# Power.net
KiCad netlist of a schematic drawn in Altium Designer
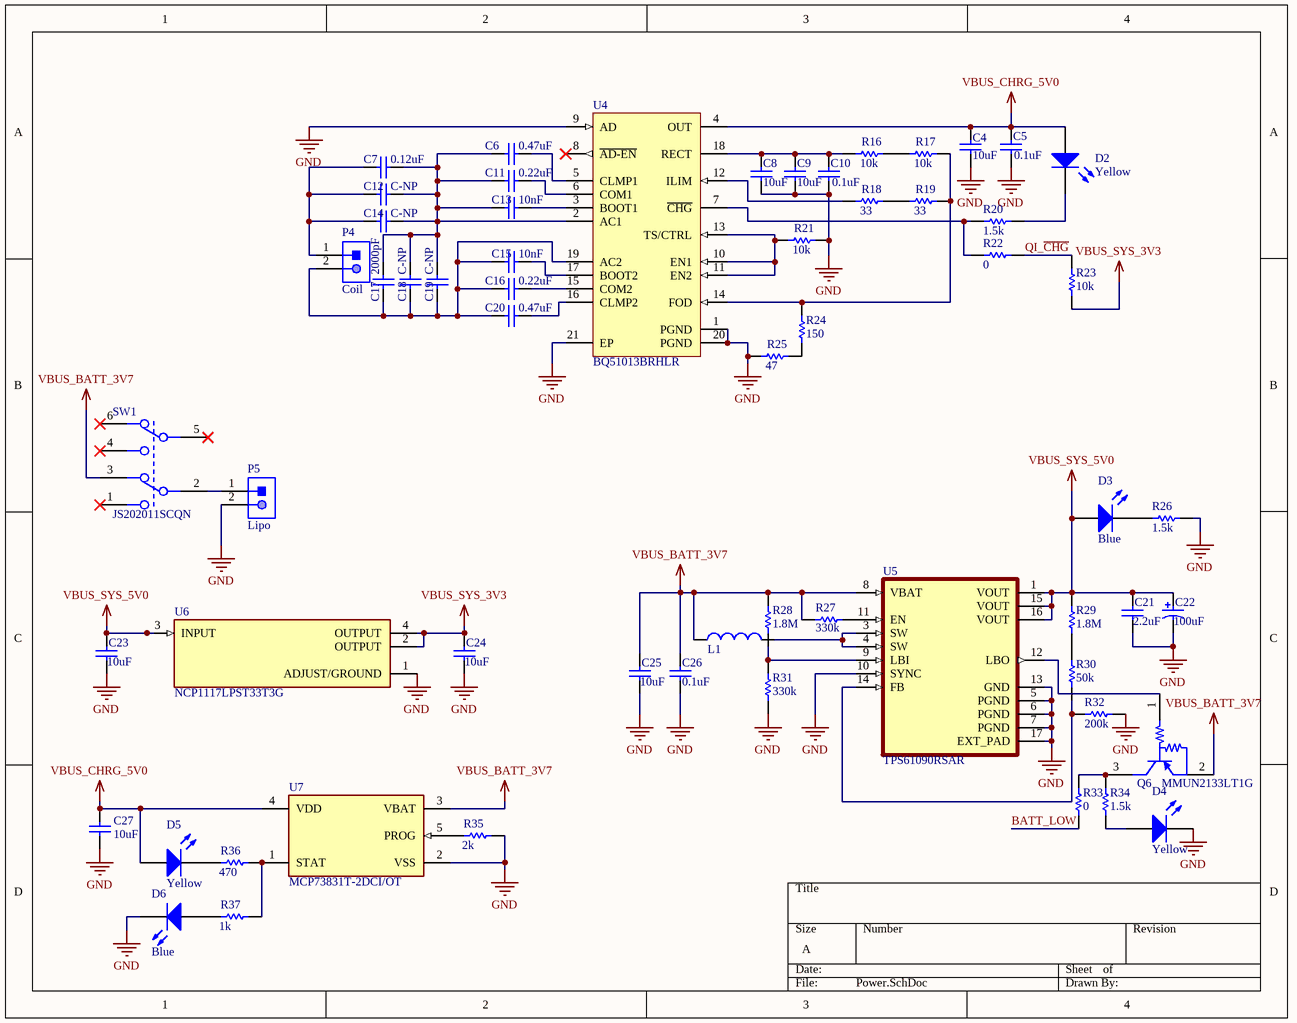
[diagram p0: Power.SchDoc]

(export (version "E")
  (design (tool "Eeschema 10.0.6"))
  (components
    (comp (ref "C4")
      (value "10uF")
      (footprint "0603")
      (description "10uF, 10%, 25V")
      (fields (field (name "GFUPARTNO") "C1608C0G1H361J"))
      (libsource (lib "AltiumGFU") (part "Cap"))
    )
    (comp (ref "C5")
      (value "0.1uF")
      (footprint "0603")
      (description "0.1uF, 10%, 50V")
      (fields (field (name "GFUPARTNO") "C1608C0G1H361J"))
      (libsource (lib "AltiumGFU") (part "Cap"))
    )
    (comp (ref "C6")
      (value "0.47uF")
      (footprint "0603")
      (description "0.47uF, 10%, 25V")
      (fields (field (name "GFUPARTNO") "C1608C0G1H361J"))
      (libsource (lib "AltiumGFU") (part "Cap"))
    )
    (comp (ref "C7")
      (value "0.12uF")
      (footprint "0603")
      (description "0.12 uF, 10%, 25V")
      (fields (field (name "GFUPARTNO") "C1608C0G1H361J"))
      (libsource (lib "AltiumGFU") (part "Cap"))
    )
    (comp (ref "C8")
      (value "10uF")
      (footprint "0603")
      (description "10uF, 10%, 25V")
      (fields (field (name "GFUPARTNO") "C1608C0G1H361J"))
      (libsource (lib "AltiumGFU") (part "Cap"))
    )
    (comp (ref "C9")
      (value "10uF")
      (footprint "0603")
      (description "10uF, 10%, 25V")
      (fields (field (name "GFUPARTNO") "C1608C0G1H361J"))
      (libsource (lib "AltiumGFU") (part "Cap"))
    )
    (comp (ref "C10")
      (value "0.1uF")
      (footprint "0603")
      (description "0.1uF, 10%, 50V")
      (fields (field (name "GFUPARTNO") "C1608C0G1H361J"))
      (libsource (lib "AltiumGFU") (part "Cap"))
    )
    (comp (ref "C11")
      (value "0.22uF")
      (footprint "0603")
      (description "0.22uF, 10%, 25V")
      (fields (field (name "GFUPARTNO") "C1608C0G1H361J"))
      (libsource (lib "AltiumGFU") (part "Cap"))
    )
    (comp (ref "C12")
      (value "C-NP")
      (footprint "0603")
      (description "0.12 uF, 10%, 25V")
      (fields (field (name "GFUPARTNO") "C1608C0G1H361J"))
      (libsource (lib "AltiumGFU") (part "Cap"))
    )
    (comp (ref "C13")
      (value "10nF")
      (footprint "0603")
      (description "10nF, 10%, 25V")
      (fields (field (name "GFUPARTNO") "C1608C0G1H361J"))
      (libsource (lib "AltiumGFU") (part "Cap"))
    )
    (comp (ref "C14")
      (value "C-NP")
      (footprint "0603")
      (description "0.12 uF, 10%, 25V")
      (fields (field (name "GFUPARTNO") "C1608C0G1H361J"))
      (libsource (lib "AltiumGFU") (part "Cap"))
    )
    (comp (ref "C15")
      (value "10nF")
      (footprint "0603")
      (description "10nF, 10%, 25V")
      (fields (field (name "GFUPARTNO") "C1608C0G1H361J"))
      (libsource (lib "AltiumGFU") (part "Cap"))
    )
    (comp (ref "C16")
      (value "0.22uF")
      (footprint "0603")
      (description "0.22uF, 10%, 25V")
      (fields (field (name "GFUPARTNO") "C1608C0G1H361J"))
      (libsource (lib "AltiumGFU") (part "Cap"))
    )
    (comp (ref "C17")
      (value "2000pF")
      (footprint "0603")
      (description "2000 pF, 10%, 50V")
      (fields (field (name "GFUPARTNO") "C1608C0G1H361J"))
      (libsource (lib "AltiumGFU") (part "Cap"))
    )
    (comp (ref "C18")
      (value "C-NP")
      (footprint "0603")
      (description "2000 pF, 10%, 50V")
      (fields (field (name "GFUPARTNO") "C1608C0G1H361J"))
      (libsource (lib "AltiumGFU") (part "Cap"))
    )
    (comp (ref "C19")
      (value "C-NP")
      (footprint "0603")
      (description "2000 pF, 10%, 50V")
      (fields (field (name "GFUPARTNO") "C1608C0G1H361J"))
      (libsource (lib "AltiumGFU") (part "Cap"))
    )
    (comp (ref "C20")
      (value "0.47uF")
      (footprint "0603")
      (description "0.47uF, 10%, 25V")
      (fields (field (name "GFUPARTNO") "C1608C0G1H361J"))
      (libsource (lib "AltiumGFU") (part "Cap"))
    )
    (comp (ref "C21")
      (value "2.2uF")
      (footprint "0805")
      (description "1.5nF, 10%, 50V")
      (fields (field (name "GFUPARTNO") "CC0805KRX7R9BB152"))
      (libsource (lib "AltiumGFU") (part "Cap"))
    )
    (comp (ref "C22")
      (value "100uF")
      (footprint "PNSC-FP-V-C_V")
      (description "EEE-HA Series 6.3 V 100 uF Ø 5 x 5.4 mm 105 °C SMT V-Chip Aluminum Electrolytic. EEE-HA0J101WR")
      (fields (field (name "MANUFACTURER") "Panasonic"))
      (libsource (lib "Altium Content Vault") (part "CAP-P-2"))
    )
    (comp (ref "C23")
      (value "10uF")
      (footprint "0805")
      (description "1.5nF, 10%, 50V")
      (fields (field (name "GFUPARTNO") "CC0805KRX7R9BB152"))
      (libsource (lib "AltiumGFU") (part "Cap"))
    )
    (comp (ref "C24")
      (value "10uF")
      (footprint "0805")
      (description "1.5nF, 10%, 50V")
      (fields (field (name "GFUPARTNO") "CC0805KRX7R9BB152"))
      (libsource (lib "AltiumGFU") (part "Cap"))
    )
    (comp (ref "C25")
      (value "10uF")
      (footprint "0805")
      (description "1.5nF, 10%, 50V")
      (fields (field (name "GFUPARTNO") "CC0805KRX7R9BB152"))
      (libsource (lib "AltiumGFU") (part "Cap"))
    )
    (comp (ref "C26")
      (value "0.1uF")
      (footprint "0805")
      (description "1.5nF, 10%, 50V")
      (fields (field (name "GFUPARTNO") "CC0805KRX7R9BB152"))
      (libsource (lib "AltiumGFU") (part "Cap"))
    )
    (comp (ref "C27")
      (value "10uF")
      (footprint "0805")
      (description "1.5nF, 10%, 50V")
      (fields (field (name "GFUPARTNO") "CC0805KRX7R9BB152"))
      (libsource (lib "AltiumGFU") (part "Cap"))
    )
    (comp (ref "D2")
      (value "Yellow")
      (footprint "1206_A_LED")
      (libsource (lib "WE-LED_K1A2-2") (part "WE-LED_K1A2-2_Local"))
    )
    (comp (ref "D3")
      (value "Blue")
      (footprint "1206_A_LED")
      (libsource (lib "WE-LED_K1A2-2") (part "WE-LED_K1A2-2_Local"))
    )
    (comp (ref "D4")
      (value "Yellow")
      (footprint "1206_A_LED")
      (libsource (lib "WE-LED_K1A2-2") (part "WE-LED_K1A2-2_Local"))
    )
    (comp (ref "D5")
      (value "Yellow")
      (footprint "1206_A_LED")
      (libsource (lib "WE-LED_K1A2-2") (part "WE-LED_K1A2-2_Local"))
    )
    (comp (ref "D6")
      (value "Blue")
      (footprint "1206_A_LED")
      (libsource (lib "WE-LED_K1A2-2") (part "WE-LED_K1A2-2_Local"))
    )
    (comp (ref "L1")
      (value "MSS6132-472MLB")
      (footprint "COILCRAFT MSS6132 SERIES")
      (description "INDUCTOR POWER 4.7UH SHIELDED SMD")
      (fields (field (name "TOLERANCE") "20%"))
      (libsource (lib "AltiumGFU") (part "Inductor"))
    )
    (comp (ref "P4")
      (value "Coil")
      (footprint "JST-S2B-PH-K-S_V")
      (fields (field (name "TOLERANCE") "20%"))
      (libsource (lib "Altium Content Vault") (part "CN-1P-M-R2"))
    )
    (comp (ref "P5")
      (value "Lipo")
      (footprint "JST-S2B-PH-K-S_V")
      (fields (field (name "TOLERANCE") "20%"))
      (libsource (lib "Altium Content Vault") (part "CN-1P-M-R2"))
    )
    (comp (ref "Q6")
      (value "MMUN2133LT1G")
      (footprint "ONSC-SOT-23-3-318-08_V")
      (fields (field (name "MANUFACTURER") "On Semiconductor"))
      (libsource (lib "Altium Content Vault") (part "ONSC-BRT-PNP-B1E2C3-3_A"))
    )
    (comp (ref "R16")
      (value "10k")
      (footprint "0603_RES_HD")
      (description "RES 10k OHM 1/10W 5% 0603 SMD")
      (fields (field (name "GFUPARTNO") "RC0603JR-0718RL"))
      (libsource (lib "AltiumGFU") (part "ResBasic"))
    )
    (comp (ref "R17")
      (value "10k")
      (footprint "0603_RES_HD")
      (description "RES 10k OHM 1/10W 5% 0603 SMD")
      (fields (field (name "GFUPARTNO") "RC0603JR-0718RL"))
      (libsource (lib "AltiumGFU") (part "ResBasic"))
    )
    (comp (ref "R18")
      (value "33")
      (footprint "0603_RES_HD")
      (description "RES 33 OHM 1/10W 5% 0603 SMD")
      (fields (field (name "GFUPARTNO") "RC0603JR-0718RL"))
      (libsource (lib "AltiumGFU") (part "ResBasic"))
    )
    (comp (ref "R19")
      (value "33")
      (footprint "0603_RES_HD")
      (description "RES 33 OHM 1/10W 5% 0603 SMD")
      (fields (field (name "GFUPARTNO") "RC0603JR-0718RL"))
      (libsource (lib "AltiumGFU") (part "ResBasic"))
    )
    (comp (ref "R20")
      (value "1.5k")
      (footprint "0603_RES_HD")
      (description "RES 1.5k OHM 1/10W 5% 0603 SMD")
      (fields (field (name "GFUPARTNO") "RC0603JR-0718RL"))
      (libsource (lib "AltiumGFU") (part "ResBasic"))
    )
    (comp (ref "R21")
      (value "10k")
      (footprint "0603_RES_HD")
      (description "RES 10k OHM 1/10W 5% 0603 SMD")
      (fields (field (name "GFUPARTNO") "RC0603JR-0718RL"))
      (libsource (lib "AltiumGFU") (part "ResBasic"))
    )
    (comp (ref "R22")
      (value "0")
      (footprint "0603_RES_HD")
      (description "RES 1.5k OHM 1/10W 5% 0603 SMD")
      (fields (field (name "GFUPARTNO") "RC0603JR-0718RL"))
      (libsource (lib "AltiumGFU") (part "ResBasic"))
    )
    (comp (ref "R23")
      (value "10k")
      (footprint "0603_RES_HD")
      (description "RES 1.5k OHM 1/10W 5% 0603 SMD")
      (fields (field (name "GFUPARTNO") "RC0603JR-0718RL"))
      (libsource (lib "AltiumGFU") (part "ResBasic"))
    )
    (comp (ref "R24")
      (value "150")
      (footprint "0603_RES_HD")
      (description "RES 150 OHM 1/10W 5% 0603 SMD")
      (fields (field (name "GFUPARTNO") "RC0603JR-0718RL"))
      (libsource (lib "AltiumGFU") (part "ResBasic"))
    )
    (comp (ref "R25")
      (value "47")
      (footprint "0603_RES_HD")
      (description "RES 47 OHM 1/10W 5% 0603 SMD")
      (fields (field (name "GFUPARTNO") "RC0603JR-0718RL"))
      (libsource (lib "AltiumGFU") (part "ResBasic"))
    )
    (comp (ref "R26")
      (value "1.5k")
      (footprint "0805_RES_HD")
      (description "1.5kOhm ±1% 0.125W, 1/8W Surface Mount Resistor Thick Film ±100ppm/°C 0805")
      (fields (field (name "GFUPARTNO") "RC0805FR-07100RL"))
      (libsource (lib "AltiumGFU") (part "ResBasic"))
    )
    (comp (ref "R27")
      (value "330k")
      (footprint "0805_RES_HD")
      (description "330kOhm ±1% 0.125W, 1/8W Surface Mount Resistor Thick Film ±100ppm/°C 0805")
      (fields (field (name "GFUPARTNO") "RC0805FR-07100RL"))
      (libsource (lib "AltiumGFU") (part "ResBasic"))
    )
    (comp (ref "R28")
      (value "1.8M")
      (footprint "0805_RES_HD")
      (description "1.8MOhm ±1% 0.125W, 1/8W Surface Mount Resistor Thick Film ±100ppm/°C 0805")
      (fields (field (name "GFUPARTNO") "RC0805FR-07100RL"))
      (libsource (lib "AltiumGFU") (part "ResBasic"))
    )
    (comp (ref "R29")
      (value "1.8M")
      (footprint "0805_RES_HD")
      (description "100 Ohm ±1% 0.125W, 1/8W Surface Mount Resistor Thick Film ±100ppm/°C 0805")
      (fields (field (name "GFUPARTNO") "RC0805FR-07100RL"))
      (libsource (lib "AltiumGFU") (part "ResBasic"))
    )
    (comp (ref "R30")
      (value "50k")
      (footprint "0805_RES_HD")
      (description "50k Ohm ±1% 0.125W, 1/8W Surface Mount Resistor Thick Film ±100ppm/°C 0805")
      (fields (field (name "GFUPARTNO") "RC0805FR-07100RL"))
      (libsource (lib "AltiumGFU") (part "ResBasic"))
    )
    (comp (ref "R31")
      (value "330k")
      (footprint "0805_RES_HD")
      (description "330kOhm ±1% 0.125W, 1/8W Surface Mount Resistor Thick Film ±100ppm/°C 0805")
      (fields (field (name "GFUPARTNO") "RC0805FR-07100RL"))
      (libsource (lib "AltiumGFU") (part "ResBasic"))
    )
    (comp (ref "R32")
      (value "200k")
      (footprint "0805_RES_HD")
      (description "50k Ohm ±1% 0.125W, 1/8W Surface Mount Resistor Thick Film ±100ppm/°C 0805")
      (fields (field (name "GFUPARTNO") "RC0805FR-07100RL"))
      (libsource (lib "AltiumGFU") (part "ResBasic"))
    )
    (comp (ref "R33")
      (value "0")
      (footprint "0805_RES_HD")
      (description "1.5kOhm ±1% 0.125W, 1/8W Surface Mount Resistor Thick Film ±100ppm/°C 0805")
      (fields (field (name "GFUPARTNO") "RC0805FR-07100RL"))
      (libsource (lib "AltiumGFU") (part "ResBasic"))
    )
    (comp (ref "R34")
      (value "1.5k")
      (footprint "0805_RES_HD")
      (description "1.5kOhm ±1% 0.125W, 1/8W Surface Mount Resistor Thick Film ±100ppm/°C 0805")
      (fields (field (name "GFUPARTNO") "RC0805FR-07100RL"))
      (libsource (lib "AltiumGFU") (part "ResBasic"))
    )
    (comp (ref "R35")
      (value "2k")
      (footprint "0805_RES_HD")
      (description "20kOhm ±1% 0.125W, 1/8W Surface Mount Resistor Thick Film ±100ppm/°C 0805")
      (fields (field (name "GFUPARTNO") "RC0805FR-07100RL"))
      (libsource (lib "AltiumGFU") (part "ResBasic"))
    )
    (comp (ref "R36")
      (value "470")
      (footprint "0805_RES_HD")
      (description "470Ohm ±1% 0.125W, 1/8W Surface Mount Resistor Thick Film ±100ppm/°C 0805")
      (fields (field (name "GFUPARTNO") "RC0805FR-07100RL"))
      (libsource (lib "AltiumGFU") (part "ResBasic"))
    )
    (comp (ref "R37")
      (value "1k")
      (footprint "0805_RES_HD")
      (description "470Ohm ±1% 0.125W, 1/8W Surface Mount Resistor Thick Film ±100ppm/°C 0805")
      (fields (field (name "GFUPARTNO") "RC0805FR-07100RL"))
      (libsource (lib "AltiumGFU") (part "ResBasic"))
    )
    (comp (ref "SW1")
      (value "JS202011SCQN")
      (footprint "FP-JS202011SCQN-MFG")
      (description "SWITCH SLIDE DPDT 300MA 6V")
      (libsource (lib "Altium Content Vault") (part "ac99ea1af431c19115f5225061c5c88"))
    )
    (comp (ref "U4")
      (value "BQ51013BRHLR")
      (footprint "RHL0020A_V")
      (fields (field (name "PARTNUMBER") "BQ51013B"))
      (libsource (lib "Altium Content Vault") (part "TI-BQ51013B-RHL20"))
    )
    (comp (ref "U5")
      (value "TPS61090RSAR")
      (footprint "QFN65P400X400X100-17N")
      (description "1.8Vin, 2A Switch, 96% Efficient Boost Converter 16-QFN -40 to 85")
      (fields (field (name "MF") "Texas Instruments"))
      (libsource (lib "TPS61090RSAR") (part "TPS61090RSAR"))
    )
    (comp (ref "U6")
      (value "NCP1117LPST33T3G")
      (footprint "FP-318H-MFG")
      (description "IC REG LINEAR 3.3V 1A SOT223")
      (libsource (lib "Altium Content Vault") (part "ba9dfc6f1948e29eb9591bef83395b3"))
    )
    (comp (ref "U7")
      (value "MCP73831T-2DCI/OT")
      (footprint "FP-C04-091-OT-IPC_B")
      (description "IC CONTROLLR LI-ION 4.2V SOT23-5")
      (libsource (lib "Altium Content Vault") (part "61f5a3bb3429d9e0caadea342aa3b19"))
    )
  )
  (nets
    (net (code "1") (name "/BATT_LOW") (class "Default")
      (node (ref "R33") (pin "1") (pinfunction "1_1") (pintype "passive"))
    )
    (net (code "2") (name "/QI_~{CHG}") (class "Default")
      (node (ref "R22") (pin "1") (pinfunction "1_1") (pintype "passive"))
      (node (ref "R23") (pin "2") (pinfunction "2_2") (pintype "passive"))
    )
    (net (code "3") (name "GND") (class "Default")
      (node (ref "C10") (pin "1") (pinfunction "1_1") (pintype "passive"))
      (node (ref "C21") (pin "2") (pinfunction "2_2") (pintype "passive"))
      (node (ref "C22") (pin "2") (pinfunction "2_2") (pintype "passive"))
      (node (ref "C23") (pin "2") (pinfunction "2_2") (pintype "passive"))
      (node (ref "C24") (pin "2") (pinfunction "2_2") (pintype "passive"))
      (node (ref "C25") (pin "2") (pinfunction "2_2") (pintype "passive"))
      (node (ref "C26") (pin "2") (pinfunction "2_2") (pintype "passive"))
      (node (ref "C27") (pin "2") (pinfunction "2_2") (pintype "passive"))
      (node (ref "C4") (pin "1") (pinfunction "1_1") (pintype "passive"))
      (node (ref "C5") (pin "1") (pinfunction "1_1") (pintype "passive"))
      (node (ref "C8") (pin "1") (pinfunction "1_1") (pintype "passive"))
      (node (ref "C9") (pin "1") (pinfunction "1_1") (pintype "passive"))
      (node (ref "D4") (pin "1") (pinfunction "K_1") (pintype "passive"))
      (node (ref "D6") (pin "1") (pinfunction "K_1") (pintype "passive"))
      (node (ref "P5") (pin "2") (pinfunction "2_2") (pintype "passive"))
      (node (ref "R21") (pin "2") (pinfunction "2_2") (pintype "passive"))
      (node (ref "R25") (pin "1") (pinfunction "1_1") (pintype "passive"))
      (node (ref "R26") (pin "1") (pinfunction "1_1") (pintype "passive"))
      (node (ref "R31") (pin "1") (pinfunction "1_1") (pintype "passive"))
      (node (ref "R32") (pin "2") (pinfunction "2_2") (pintype "passive"))
      (node (ref "R35") (pin "2") (pinfunction "2_2") (pintype "passive"))
      (node (ref "U4") (pin "1") (pinfunction "PGND_1") (pintype "power_in"))
      (node (ref "U4") (pin "20") (pinfunction "PGND_20") (pintype "power_in"))
      (node (ref "U4") (pin "21") (pinfunction "EP_21") (pintype "passive"))
      (node (ref "U4") (pin "9") (pinfunction "AD_9") (pintype "input"))
      (node (ref "U5") (pin "10") (pinfunction "SYNC_10") (pintype "input"))
      (node (ref "U5") (pin "13") (pinfunction "GND_13") (pintype "power_in"))
      (node (ref "U5") (pin "17") (pinfunction "EXT_PAD_17") (pintype "power_in"))
      (node (ref "U5") (pin "5") (pinfunction "PGND_5") (pintype "power_in"))
      (node (ref "U5") (pin "6") (pinfunction "PGND_6") (pintype "power_in"))
      (node (ref "U5") (pin "7") (pinfunction "PGND_7") (pintype "power_in"))
      (node (ref "U6") (pin "1") (pinfunction "ADJUST/GROUND_1") (pintype "power_in"))
      (node (ref "U7") (pin "2") (pinfunction "VSS_2") (pintype "power_in"))
    )
    (net (code "4") (name "Net-(C12-Pad2)") (class "Default")
      (node (ref "C12") (pin "2") (pinfunction "2_2") (pintype "passive"))
      (node (ref "C14") (pin "2") (pinfunction "2_2") (pintype "passive"))
      (node (ref "C7") (pin "2") (pinfunction "2_2") (pintype "passive"))
      (node (ref "P4") (pin "1") (pinfunction "1_1") (pintype "passive"))
    )
    (net (code "5") (name "Net-(D2-K)") (class "Default")
      (node (ref "D2") (pin "1") (pinfunction "K_1") (pintype "passive"))
      (node (ref "R20") (pin "1") (pinfunction "1_1") (pintype "passive"))
    )
    (net (code "6") (name "Net-(D3-K)") (class "Default")
      (node (ref "D3") (pin "1") (pinfunction "K_1") (pintype "passive"))
      (node (ref "R26") (pin "2") (pinfunction "2_2") (pintype "passive"))
    )
    (net (code "7") (name "Net-(D4-A)") (class "Default")
      (node (ref "D4") (pin "2") (pinfunction "A_2") (pintype "passive"))
      (node (ref "R34") (pin "1") (pinfunction "1_1") (pintype "passive"))
    )
    (net (code "8") (name "Net-(D5-K)") (class "Default")
      (node (ref "D5") (pin "1") (pinfunction "K_1") (pintype "passive"))
      (node (ref "R36") (pin "1") (pinfunction "1_1") (pintype "passive"))
    )
    (net (code "9") (name "Net-(D6-A)") (class "Default")
      (node (ref "D6") (pin "2") (pinfunction "A_2") (pintype "passive"))
      (node (ref "R37") (pin "1") (pinfunction "1_1") (pintype "passive"))
    )
    (net (code "10") (name "Net-(L1-Pad2)") (class "Default")
      (node (ref "L1") (pin "2") (pinfunction "2_2") (pintype "passive"))
      (node (ref "U5") (pin "3") (pinfunction "SW_3") (pintype "input"))
      (node (ref "U5") (pin "4") (pinfunction "SW_4") (pintype "input"))
    )
    (net (code "11") (name "Net-(P5-Pad1)") (class "Default")
      (node (ref "P5") (pin "1") (pinfunction "1_1") (pintype "passive"))
      (node (ref "SW1") (pin "2") (pinfunction "2_2") (pintype "passive"))
    )
    (net (code "12") (name "Net-(Q6-B)") (class "Default")
      (node (ref "Q6") (pin "1") (pinfunction "B_1") (pintype "passive"))
      (node (ref "U5") (pin "12") (pinfunction "LBO_12") (pintype "output"))
    )
    (net (code "13") (name "Net-(Q6-C)") (class "Default")
      (node (ref "Q6") (pin "3") (pinfunction "C_3") (pintype "passive"))
      (node (ref "R33") (pin "2") (pinfunction "2_2") (pintype "passive"))
      (node (ref "R34") (pin "2") (pinfunction "2_2") (pintype "passive"))
    )
    (net (code "14") (name "Net-(R16-Pad2)") (class "Default")
      (node (ref "R16") (pin "2") (pinfunction "2_2") (pintype "passive"))
      (node (ref "R17") (pin "1") (pinfunction "1_1") (pintype "passive"))
    )
    (net (code "15") (name "Net-(R18-Pad2)") (class "Default")
      (node (ref "R18") (pin "2") (pinfunction "2_2") (pintype "passive"))
      (node (ref "R19") (pin "1") (pinfunction "1_1") (pintype "passive"))
    )
    (net (code "16") (name "Net-(R24-Pad1)") (class "Default")
      (node (ref "R24") (pin "1") (pinfunction "1_1") (pintype "passive"))
      (node (ref "R25") (pin "2") (pinfunction "2_2") (pintype "passive"))
    )
    (net (code "17") (name "Net-(R29-Pad1)") (class "Default")
      (node (ref "R29") (pin "1") (pinfunction "1_1") (pintype "passive"))
      (node (ref "R30") (pin "1") (pinfunction "1_1") (pintype "passive"))
    )
    (net (code "18") (name "Net-(U4-AC1)") (class "Default")
      (node (ref "C11") (pin "2") (pinfunction "2_2") (pintype "passive"))
      (node (ref "C12") (pin "1") (pinfunction "1_1") (pintype "passive"))
      (node (ref "C13") (pin "2") (pinfunction "2_2") (pintype "passive"))
      (node (ref "C14") (pin "1") (pinfunction "1_1") (pintype "passive"))
      (node (ref "C17") (pin "1") (pinfunction "1_1") (pintype "passive"))
      (node (ref "C18") (pin "1") (pinfunction "1_1") (pintype "passive"))
      (node (ref "C19") (pin "1") (pinfunction "1_1") (pintype "passive"))
      (node (ref "C6") (pin "2") (pinfunction "2_2") (pintype "passive"))
      (node (ref "C7") (pin "1") (pinfunction "1_1") (pintype "passive"))
      (node (ref "U4") (pin "2") (pinfunction "AC1_2") (pintype "power_in"))
    )
    (net (code "19") (name "Net-(U4-AC2)") (class "Default")
      (node (ref "C15") (pin "2") (pinfunction "2_2") (pintype "passive"))
      (node (ref "C16") (pin "2") (pinfunction "2_2") (pintype "passive"))
      (node (ref "C17") (pin "2") (pinfunction "2_2") (pintype "passive"))
      (node (ref "C18") (pin "2") (pinfunction "2_2") (pintype "passive"))
      (node (ref "C19") (pin "2") (pinfunction "2_2") (pintype "passive"))
      (node (ref "C20") (pin "2") (pinfunction "2_2") (pintype "passive"))
      (node (ref "P4") (pin "2") (pinfunction "2_2") (pintype "passive"))
      (node (ref "U4") (pin "19") (pinfunction "AC2_19") (pintype "power_in"))
    )
    (net (code "20") (name "Net-(U4-BOOT1)") (class "Default")
      (node (ref "C13") (pin "1") (pinfunction "1_1") (pintype "passive"))
      (node (ref "U4") (pin "3") (pinfunction "BOOT1_3") (pintype "passive"))
    )
    (net (code "21") (name "Net-(U4-BOOT2)") (class "Default")
      (node (ref "C15") (pin "1") (pinfunction "1_1") (pintype "passive"))
      (node (ref "U4") (pin "17") (pinfunction "BOOT2_17") (pintype "passive"))
    )
    (net (code "22") (name "Net-(U4-CLMP1)") (class "Default")
      (node (ref "C6") (pin "1") (pinfunction "1_1") (pintype "passive"))
      (node (ref "U4") (pin "5") (pinfunction "CLMP1_5") (pintype "open_collector"))
    )
    (net (code "23") (name "Net-(U4-CLMP2)") (class "Default")
      (node (ref "C20") (pin "1") (pinfunction "1_1") (pintype "passive"))
      (node (ref "U4") (pin "16") (pinfunction "CLMP2_16") (pintype "open_collector"))
    )
    (net (code "24") (name "Net-(U4-COM1)") (class "Default")
      (node (ref "C11") (pin "1") (pinfunction "1_1") (pintype "passive"))
      (node (ref "U4") (pin "6") (pinfunction "COM1_6") (pintype "open_collector"))
    )
    (net (code "25") (name "Net-(U4-COM2)") (class "Default")
      (node (ref "C16") (pin "1") (pinfunction "1_1") (pintype "passive"))
      (node (ref "U4") (pin "15") (pinfunction "COM2_15") (pintype "open_collector"))
    )
    (net (code "26") (name "Net-(U4-EN1)") (class "Default")
      (node (ref "R21") (pin "1") (pinfunction "1_1") (pintype "passive"))
      (node (ref "U4") (pin "10") (pinfunction "EN1_10") (pintype "input"))
      (node (ref "U4") (pin "11") (pinfunction "EN2_11") (pintype "input"))
      (node (ref "U4") (pin "13") (pinfunction "TS/CTRL_13") (pintype "input"))
    )
    (net (code "27") (name "Net-(U4-FOD)") (class "Default")
      (node (ref "R17") (pin "2") (pinfunction "2_2") (pintype "passive"))
      (node (ref "R19") (pin "2") (pinfunction "2_2") (pintype "passive"))
      (node (ref "R24") (pin "2") (pinfunction "2_2") (pintype "passive"))
      (node (ref "U4") (pin "14") (pinfunction "FOD_14") (pintype "input"))
    )
    (net (code "28") (name "Net-(U4-ILIM)") (class "Default")
      (node (ref "R18") (pin "1") (pinfunction "1_1") (pintype "passive"))
      (node (ref "U4") (pin "12") (pinfunction "ILIM_12") (pintype "input"))
    )
    (net (code "29") (name "Net-(U4-RECT)") (class "Default")
      (node (ref "C10") (pin "2") (pinfunction "2_2") (pintype "passive"))
      (node (ref "C8") (pin "2") (pinfunction "2_2") (pintype "passive"))
      (node (ref "C9") (pin "2") (pinfunction "2_2") (pintype "passive"))
      (node (ref "R16") (pin "1") (pinfunction "1_1") (pintype "passive"))
      (node (ref "U4") (pin "18") (pinfunction "RECT_18") (pintype "passive"))
    )
    (net (code "30") (name "Net-(U4-~{CHG})") (class "Default")
      (node (ref "R20") (pin "2") (pinfunction "2_2") (pintype "passive"))
      (node (ref "R22") (pin "2") (pinfunction "2_2") (pintype "passive"))
      (node (ref "U4") (pin "7") (pinfunction "~{CHG}_7") (pintype "open_collector"))
    )
    (net (code "31") (name "Net-(U5-EN)") (class "Default")
      (node (ref "R27") (pin "2") (pinfunction "2_2") (pintype "passive"))
      (node (ref "U5") (pin "11") (pinfunction "EN_11") (pintype "input"))
    )
    (net (code "32") (name "Net-(U5-FB)") (class "Default")
      (node (ref "R30") (pin "2") (pinfunction "2_2") (pintype "passive"))
      (node (ref "R32") (pin "1") (pinfunction "1_1") (pintype "passive"))
      (node (ref "U5") (pin "14") (pinfunction "FB_14") (pintype "input"))
    )
    (net (code "33") (name "Net-(U5-LBI)") (class "Default")
      (node (ref "R28") (pin "1") (pinfunction "1_1") (pintype "passive"))
      (node (ref "R31") (pin "2") (pinfunction "2_2") (pintype "passive"))
      (node (ref "U5") (pin "9") (pinfunction "LBI_9") (pintype "input"))
    )
    (net (code "34") (name "Net-(U7-PROG)") (class "Default")
      (node (ref "R35") (pin "1") (pinfunction "1_1") (pintype "passive"))
      (node (ref "U7") (pin "5") (pinfunction "PROG_5") (pintype "input"))
    )
    (net (code "35") (name "Net-(U7-STAT)") (class "Default")
      (node (ref "R36") (pin "2") (pinfunction "2_2") (pintype "passive"))
      (node (ref "R37") (pin "2") (pinfunction "2_2") (pintype "passive"))
      (node (ref "U7") (pin "1") (pinfunction "STAT_1") (pintype "passive"))
    )
    (net (code "36") (name "VBUS_BATT_3V7") (class "Default")
      (node (ref "C25") (pin "1") (pinfunction "1_1") (pintype "passive"))
      (node (ref "C26") (pin "1") (pinfunction "1_1") (pintype "passive"))
      (node (ref "L1") (pin "1") (pinfunction "1_1") (pintype "passive"))
      (node (ref "Q6") (pin "2") (pinfunction "E_2") (pintype "passive"))
      (node (ref "R27") (pin "1") (pinfunction "1_1") (pintype "passive"))
      (node (ref "R28") (pin "2") (pinfunction "2_2") (pintype "passive"))
      (node (ref "SW1") (pin "3") (pinfunction "3_3") (pintype "passive"))
      (node (ref "U5") (pin "8") (pinfunction "VBAT_8") (pintype "input"))
      (node (ref "U7") (pin "3") (pinfunction "VBAT_3") (pintype "power_in"))
    )
    (net (code "37") (name "VBUS_CHRG_5V0") (class "Default")
      (node (ref "C27") (pin "1") (pinfunction "1_1") (pintype "passive"))
      (node (ref "C4") (pin "2") (pinfunction "2_2") (pintype "passive"))
      (node (ref "C5") (pin "2") (pinfunction "2_2") (pintype "passive"))
      (node (ref "D2") (pin "2") (pinfunction "A_2") (pintype "passive"))
      (node (ref "D5") (pin "2") (pinfunction "A_2") (pintype "passive"))
      (node (ref "U4") (pin "4") (pinfunction "OUT_4") (pintype "power_in"))
      (node (ref "U7") (pin "4") (pinfunction "VDD_4") (pintype "power_in"))
    )
    (net (code "38") (name "VBUS_SYS_3V3") (class "Default")
      (node (ref "C24") (pin "1") (pinfunction "1_1") (pintype "passive"))
      (node (ref "R23") (pin "1") (pinfunction "1_1") (pintype "passive"))
      (node (ref "U6") (pin "2") (pinfunction "OUTPUT_2") (pintype "power_in"))
      (node (ref "U6") (pin "4") (pinfunction "OUTPUT_4") (pintype "power_in"))
    )
    (net (code "39") (name "VBUS_SYS_5V0") (class "Default")
      (node (ref "C21") (pin "1") (pinfunction "1_1") (pintype "passive"))
      (node (ref "C22") (pin "1") (pinfunction "1_1") (pintype "passive"))
      (node (ref "C23") (pin "1") (pinfunction "1_1") (pintype "passive"))
      (node (ref "D3") (pin "2") (pinfunction "A_2") (pintype "passive"))
      (node (ref "R29") (pin "2") (pinfunction "2_2") (pintype "passive"))
      (node (ref "U5") (pin "1") (pinfunction "VOUT_1") (pintype "power_in"))
      (node (ref "U5") (pin "15") (pinfunction "VOUT_15") (pintype "power_in"))
      (node (ref "U5") (pin "16") (pinfunction "VOUT_16") (pintype "power_in"))
      (node (ref "U6") (pin "3") (pinfunction "INPUT_3") (pintype "input"))
    )
    (net (code "40") (name "unconnected-(SW1-Pad1)") (class "Default")
      (node (ref "SW1") (pin "1") (pinfunction "1_1") (pintype "passive+no_connect"))
    )
    (net (code "41") (name "unconnected-(SW1-Pad4)") (class "Default")
      (node (ref "SW1") (pin "4") (pinfunction "4_4") (pintype "passive+no_connect"))
    )
    (net (code "42") (name "unconnected-(SW1-Pad5)") (class "Default")
      (node (ref "SW1") (pin "5") (pinfunction "5_5") (pintype "passive+no_connect"))
    )
    (net (code "43") (name "unconnected-(SW1-Pad6)") (class "Default")
      (node (ref "SW1") (pin "6") (pinfunction "6_6") (pintype "passive+no_connect"))
    )
    (net (code "44") (name "unconnected-(U4-~{AD-EN}-Pad8)") (class "Default")
      (node (ref "U4") (pin "8") (pinfunction "~{AD-EN}_8") (pintype "output+no_connect"))
    )
  )
)
